# MCU.net
KiCad netlist of a schematic drawn in Altium Designer
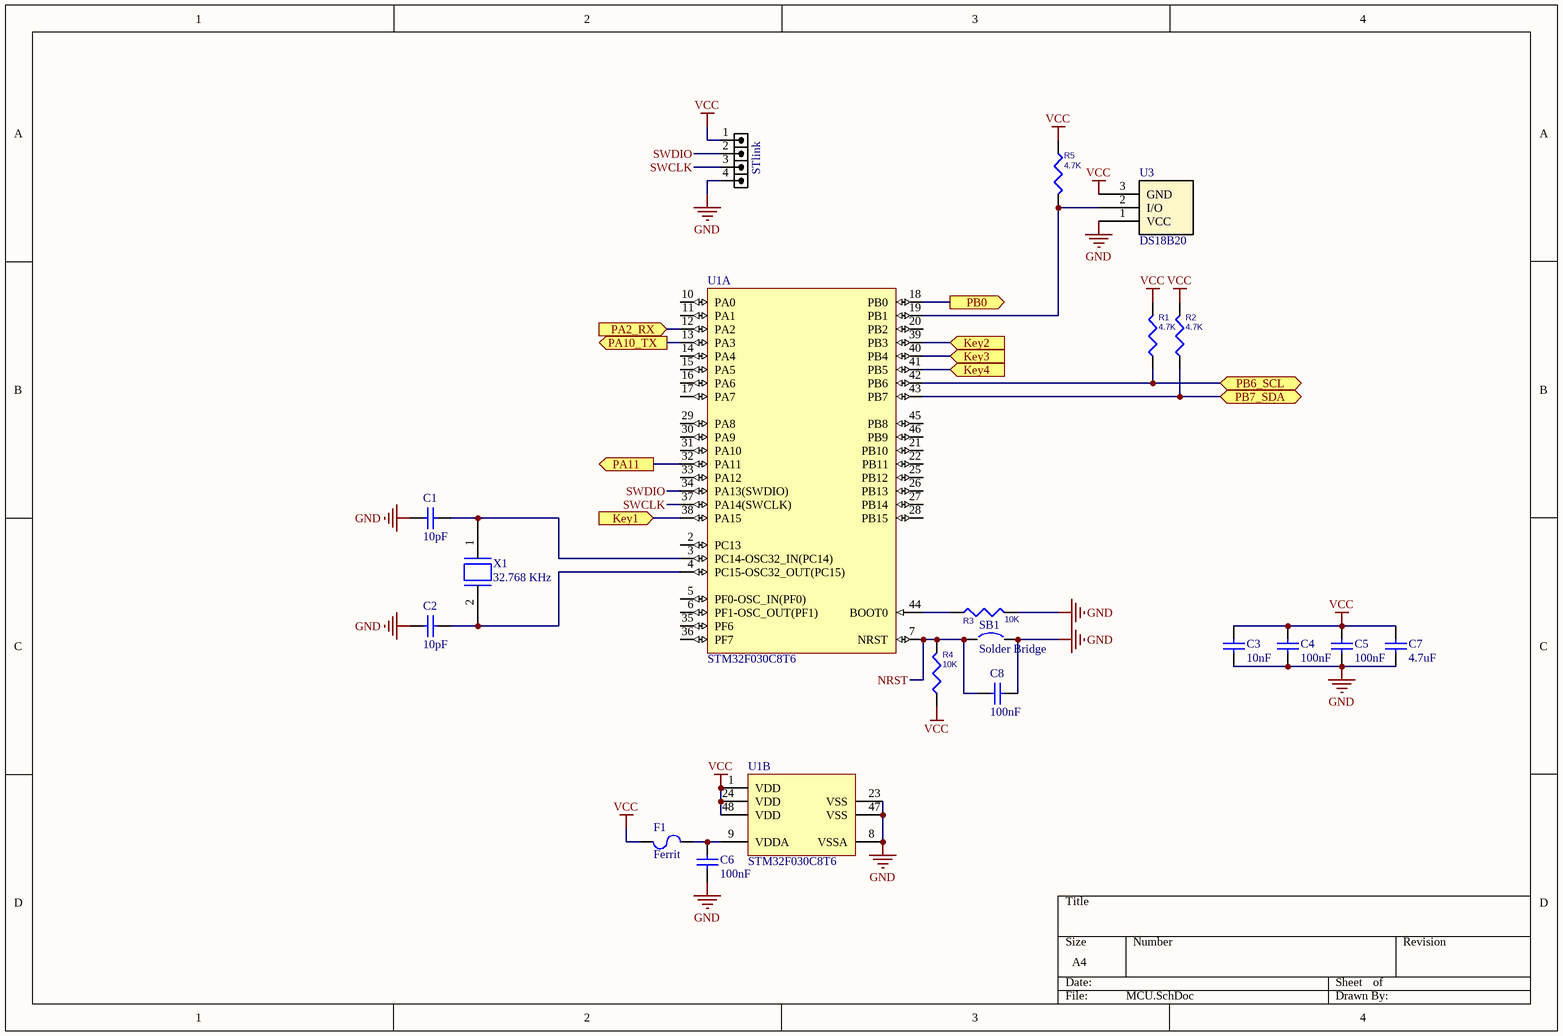
[diagram p0: MCU.SchDoc]

(export (version "E")
  (design (tool "Eeschema 10.0.6"))
  (components
    (comp (ref "C1")
      (value "10pF")
      (footprint "0603C")
      (description "Capacitor")
      (libsource (lib "NAHAL_LIB") (part "Cap"))
    )
    (comp (ref "C2")
      (value "10pF")
      (footprint "0603C")
      (description "Capacitor")
      (libsource (lib "NAHAL_LIB") (part "Cap"))
    )
    (comp (ref "C3")
      (value "10nF")
      (footprint "0603C")
      (description "Capacitor")
      (libsource (lib "NAHAL_LIB") (part "Cap"))
    )
    (comp (ref "C4")
      (value "100nF")
      (footprint "0603C")
      (description "Capacitor")
      (libsource (lib "NAHAL_LIB") (part "Cap"))
    )
    (comp (ref "C5")
      (value "100nF")
      (footprint "0603C")
      (description "Capacitor")
      (libsource (lib "NAHAL_LIB") (part "Cap"))
    )
    (comp (ref "C6")
      (value "100nF")
      (footprint "0603C")
      (description "Capacitor")
      (libsource (lib "NAHAL_LIB") (part "Cap"))
    )
    (comp (ref "C7")
      (value "4.7uF")
      (footprint "0603C")
      (description "Capacitor")
      (libsource (lib "NAHAL_LIB") (part "Cap"))
    )
    (comp (ref "C8")
      (value "100nF")
      (footprint "0603C")
      (description "Capacitor")
      (libsource (lib "NAHAL_LIB") (part "Cap"))
    )
    (comp (ref "F1")
      (value "Ferrit")
      (footprint "0805F")
      (description "Ferrit 0805")
      (libsource (lib "NAHAL_LIB") (part "Fuse SMD"))
    )
    (comp (ref "R1") (value "4.7K") (footprint "0603R") (libsource (lib "NAHAL_LIB") (part "R")))
    (comp (ref "R2") (value "4.7K") (footprint "0603R") (libsource (lib "NAHAL_LIB") (part "R")))
    (comp (ref "R3") (value "10K") (footprint "0603R") (libsource (lib "NAHAL_LIB") (part "R")))
    (comp (ref "R4") (value "10K") (footprint "0603R") (libsource (lib "NAHAL_LIB") (part "R")))
    (comp (ref "R5") (value "4.7K") (footprint "0603R") (libsource (lib "NAHAL_LIB") (part "R")))
    (comp (ref "SB1")
      (value "Solder Bridge")
      (footprint "Solder Bridge")
      (libsource (lib "NAHAL_LIB") (part "Solder Bridge"))
    )
    (comp (ref "STlink")
      (value "HDR1X4")
      (footprint "HDRR_M_1X4")
      (description "CONN, HEADER, RightAngle, Male, pitch: 2.54mm, 4POS")
      (libsource (lib "Conn Header") (part "HDRR_M_1X4"))
    )
    (comp (ref "U1")
      (value "STM32F030C8T6")
      (footprint "LQFP-48 7x7MM P0.5MM")
      (libsource (lib "Mcu") (part "STM32F030C8T6"))
    )
    (comp (ref "U3") (value "DS18B20") (footprint "TO-92") (libsource (lib "Salman_lib") (part "DS18B20")))
    (comp (ref "X1")
      (value "32.768 KHz")
      (footprint "32.768 - Right")
      (libsource (lib "Salman_lib") (part "XTAL"))
    )
  )
  (nets
    (net (code "1") (name "/Key1") (class "Default")
      (node (ref "U1") (pin "38") (pinfunction "PA15_38") (pintype "bidirectional"))
    )
    (net (code "2") (name "/Key2") (class "Default")
      (node (ref "U1") (pin "39") (pinfunction "PB3_39") (pintype "bidirectional"))
    )
    (net (code "3") (name "/Key3") (class "Default")
      (node (ref "U1") (pin "40") (pinfunction "PB4_40") (pintype "bidirectional"))
    )
    (net (code "4") (name "/Key4") (class "Default")
      (node (ref "U1") (pin "41") (pinfunction "PB5_41") (pintype "bidirectional"))
    )
    (net (code "5") (name "/NRST") (class "Default")
      (node (ref "C8") (pin "1") (pinfunction "1_1") (pintype "passive"))
      (node (ref "R4") (pin "2") (pinfunction "2_2") (pintype "passive"))
      (node (ref "SB1") (pin "1") (pinfunction "1_1") (pintype "passive"))
      (node (ref "U1") (pin "7") (pinfunction "NRST_7") (pintype "bidirectional"))
    )
    (net (code "6") (name "/PA2_RX") (class "Default")
      (node (ref "U1") (pin "12") (pinfunction "PA2_12") (pintype "bidirectional"))
    )
    (net (code "7") (name "/PA10_TX") (class "Default")
      (node (ref "U1") (pin "13") (pinfunction "PA3_13") (pintype "bidirectional"))
    )
    (net (code "8") (name "/PA11") (class "Default")
      (node (ref "U1") (pin "32") (pinfunction "PA11_32") (pintype "bidirectional"))
    )
    (net (code "9") (name "/PB0") (class "Default")
      (node (ref "U1") (pin "18") (pinfunction "PB0_18") (pintype "bidirectional"))
    )
    (net (code "10") (name "/PB6_SCL") (class "Default")
      (node (ref "R1") (pin "1") (pinfunction "1_1") (pintype "passive"))
      (node (ref "U1") (pin "42") (pinfunction "PB6_42") (pintype "bidirectional"))
    )
    (net (code "11") (name "/PB7_SDA") (class "Default")
      (node (ref "R2") (pin "1") (pinfunction "1_1") (pintype "passive"))
      (node (ref "U1") (pin "43") (pinfunction "PB7_43") (pintype "bidirectional"))
    )
    (net (code "12") (name "/SWCLK") (class "Default")
      (node (ref "STlink") (pin "3") (pinfunction "3_3") (pintype "passive"))
      (node (ref "U1") (pin "37") (pinfunction "PA14(SWCLK)_37") (pintype "bidirectional"))
    )
    (net (code "13") (name "/SWDIO") (class "Default")
      (node (ref "STlink") (pin "2") (pinfunction "2_2") (pintype "passive"))
      (node (ref "U1") (pin "34") (pinfunction "PA13(SWDIO)_34") (pintype "bidirectional"))
    )
    (net (code "14") (name "GND") (class "Default")
      (node (ref "C1") (pin "1") (pinfunction "1_1") (pintype "passive"))
      (node (ref "C2") (pin "1") (pinfunction "1_1") (pintype "passive"))
      (node (ref "C3") (pin "1") (pinfunction "1_1") (pintype "passive"))
      (node (ref "C4") (pin "1") (pinfunction "1_1") (pintype "passive"))
      (node (ref "C5") (pin "1") (pinfunction "1_1") (pintype "passive"))
      (node (ref "C6") (pin "1") (pinfunction "1_1") (pintype "passive"))
      (node (ref "C7") (pin "1") (pinfunction "1_1") (pintype "passive"))
      (node (ref "C8") (pin "2") (pinfunction "2_2") (pintype "passive"))
      (node (ref "R3") (pin "2") (pinfunction "2_2") (pintype "passive"))
      (node (ref "SB1") (pin "2") (pinfunction "2_2") (pintype "passive"))
      (node (ref "STlink") (pin "4") (pinfunction "4_4") (pintype "passive"))
      (node (ref "U1") (pin "23") (pinfunction "VSS_23") (pintype "power_in"))
      (node (ref "U1") (pin "47") (pinfunction "VSS_47") (pintype "power_in"))
      (node (ref "U1") (pin "8") (pinfunction "VSSA_8") (pintype "power_in"))
      (node (ref "U3") (pin "1") (pinfunction "VCC_1") (pintype "passive"))
    )
    (net (code "15") (name "Net-(U1A-BOOT0)") (class "Default")
      (node (ref "R3") (pin "1") (pinfunction "1_1") (pintype "passive"))
      (node (ref "U1") (pin "44") (pinfunction "BOOT0_44") (pintype "input"))
    )
    (net (code "16") (name "Net-(U1A-PB1)") (class "Default")
      (node (ref "R5") (pin "1") (pinfunction "1_1") (pintype "passive"))
      (node (ref "U1") (pin "19") (pinfunction "PB1_19") (pintype "bidirectional"))
      (node (ref "U3") (pin "2") (pinfunction "I/O_2") (pintype "passive"))
    )
    (net (code "17") (name "Net-(U1A-PC14-OSC32_IN(PC14))") (class "Default")
      (node (ref "C1") (pin "2") (pinfunction "2_2") (pintype "passive"))
      (node (ref "U1") (pin "3") (pinfunction "PC14-OSC32_IN(PC14)_3") (pintype "bidirectional"))
      (node (ref "X1") (pin "1") (pintype "passive"))
    )
    (net (code "18") (name "Net-(U1A-PC15-OSC32_OUT(PC15))") (class "Default")
      (node (ref "C2") (pin "2") (pinfunction "2_2") (pintype "passive"))
      (node (ref "U1") (pin "4") (pinfunction "PC15-OSC32_OUT(PC15)_4") (pintype "bidirectional"))
      (node (ref "X1") (pin "2") (pintype "passive"))
    )
    (net (code "19") (name "Net-(U1B-VDDA)") (class "Default")
      (node (ref "C6") (pin "2") (pinfunction "2_2") (pintype "passive"))
      (node (ref "F1") (pin "2") (pinfunction "2_2") (pintype "passive"))
      (node (ref "U1") (pin "9") (pinfunction "VDDA_9") (pintype "power_in"))
    )
    (net (code "20") (name "VCC") (class "Default")
      (node (ref "C3") (pin "2") (pinfunction "2_2") (pintype "passive"))
      (node (ref "C4") (pin "2") (pinfunction "2_2") (pintype "passive"))
      (node (ref "C5") (pin "2") (pinfunction "2_2") (pintype "passive"))
      (node (ref "C7") (pin "2") (pinfunction "2_2") (pintype "passive"))
      (node (ref "F1") (pin "1") (pinfunction "1_1") (pintype "passive"))
      (node (ref "R1") (pin "2") (pinfunction "2_2") (pintype "passive"))
      (node (ref "R2") (pin "2") (pinfunction "2_2") (pintype "passive"))
      (node (ref "R4") (pin "1") (pinfunction "1_1") (pintype "passive"))
      (node (ref "R5") (pin "2") (pinfunction "2_2") (pintype "passive"))
      (node (ref "STlink") (pin "1") (pinfunction "1_1") (pintype "passive"))
      (node (ref "U1") (pin "1") (pinfunction "VDD_1") (pintype "power_in"))
      (node (ref "U1") (pin "24") (pinfunction "VDD_24") (pintype "power_in"))
      (node (ref "U1") (pin "48") (pinfunction "VDD_48") (pintype "power_in"))
      (node (ref "U3") (pin "3") (pinfunction "GND_3") (pintype "passive"))
    )
    (net (code "21") (name "unconnected-(U1A-PA0-Pad10)") (class "Default")
      (node (ref "U1") (pin "10") (pinfunction "PA0_10") (pintype "bidirectional"))
    )
    (net (code "22") (name "unconnected-(U1A-PA1-Pad11)") (class "Default")
      (node (ref "U1") (pin "11") (pinfunction "PA1_11") (pintype "bidirectional"))
    )
    (net (code "23") (name "unconnected-(U1A-PA4-Pad14)") (class "Default")
      (node (ref "U1") (pin "14") (pinfunction "PA4_14") (pintype "bidirectional"))
    )
    (net (code "24") (name "unconnected-(U1A-PA5-Pad15)") (class "Default")
      (node (ref "U1") (pin "15") (pinfunction "PA5_15") (pintype "bidirectional"))
    )
    (net (code "25") (name "unconnected-(U1A-PA6-Pad16)") (class "Default")
      (node (ref "U1") (pin "16") (pinfunction "PA6_16") (pintype "bidirectional"))
    )
    (net (code "26") (name "unconnected-(U1A-PA7-Pad17)") (class "Default")
      (node (ref "U1") (pin "17") (pinfunction "PA7_17") (pintype "bidirectional"))
    )
    (net (code "27") (name "unconnected-(U1A-PA8-Pad29)") (class "Default")
      (node (ref "U1") (pin "29") (pinfunction "PA8_29") (pintype "bidirectional"))
    )
    (net (code "28") (name "unconnected-(U1A-PA9-Pad30)") (class "Default")
      (node (ref "U1") (pin "30") (pinfunction "PA9_30") (pintype "bidirectional"))
    )
    (net (code "29") (name "unconnected-(U1A-PA10-Pad31)") (class "Default")
      (node (ref "U1") (pin "31") (pinfunction "PA10_31") (pintype "bidirectional"))
    )
    (net (code "30") (name "unconnected-(U1A-PA12-Pad33)") (class "Default")
      (node (ref "U1") (pin "33") (pinfunction "PA12_33") (pintype "bidirectional"))
    )
    (net (code "31") (name "unconnected-(U1A-PB2-Pad20)") (class "Default")
      (node (ref "U1") (pin "20") (pinfunction "PB2_20") (pintype "bidirectional"))
    )
    (net (code "32") (name "unconnected-(U1A-PB8-Pad45)") (class "Default")
      (node (ref "U1") (pin "45") (pinfunction "PB8_45") (pintype "bidirectional"))
    )
    (net (code "33") (name "unconnected-(U1A-PB9-Pad46)") (class "Default")
      (node (ref "U1") (pin "46") (pinfunction "PB9_46") (pintype "bidirectional"))
    )
    (net (code "34") (name "unconnected-(U1A-PB10-Pad21)") (class "Default")
      (node (ref "U1") (pin "21") (pinfunction "PB10_21") (pintype "bidirectional"))
    )
    (net (code "35") (name "unconnected-(U1A-PB11-Pad22)") (class "Default")
      (node (ref "U1") (pin "22") (pinfunction "PB11_22") (pintype "bidirectional"))
    )
    (net (code "36") (name "unconnected-(U1A-PB12-Pad25)") (class "Default")
      (node (ref "U1") (pin "25") (pinfunction "PB12_25") (pintype "bidirectional"))
    )
    (net (code "37") (name "unconnected-(U1A-PB13-Pad26)") (class "Default")
      (node (ref "U1") (pin "26") (pinfunction "PB13_26") (pintype "bidirectional"))
    )
    (net (code "38") (name "unconnected-(U1A-PB14-Pad27)") (class "Default")
      (node (ref "U1") (pin "27") (pinfunction "PB14_27") (pintype "bidirectional"))
    )
    (net (code "39") (name "unconnected-(U1A-PB15-Pad28)") (class "Default")
      (node (ref "U1") (pin "28") (pinfunction "PB15_28") (pintype "bidirectional"))
    )
    (net (code "40") (name "unconnected-(U1A-PC13-Pad2)") (class "Default")
      (node (ref "U1") (pin "2") (pinfunction "PC13_2") (pintype "bidirectional"))
    )
    (net (code "41") (name "unconnected-(U1A-PF0-OSC_IN(PF0)-Pad5)") (class "Default")
      (node (ref "U1") (pin "5") (pinfunction "PF0-OSC_IN(PF0)_5") (pintype "bidirectional"))
    )
    (net (code "42") (name "unconnected-(U1A-PF1-OSC_OUT(PF1)-Pad6)") (class "Default")
      (node (ref "U1") (pin "6") (pinfunction "PF1-OSC_OUT(PF1)_6") (pintype "bidirectional"))
    )
    (net (code "43") (name "unconnected-(U1A-PF6-Pad35)") (class "Default")
      (node (ref "U1") (pin "35") (pinfunction "PF6_35") (pintype "bidirectional"))
    )
    (net (code "44") (name "unconnected-(U1A-PF7-Pad36)") (class "Default")
      (node (ref "U1") (pin "36") (pinfunction "PF7_36") (pintype "bidirectional"))
    )
  )
)
